# cnc_rev_1.net
KiCad netlist of a schematic drawn in EAGLE
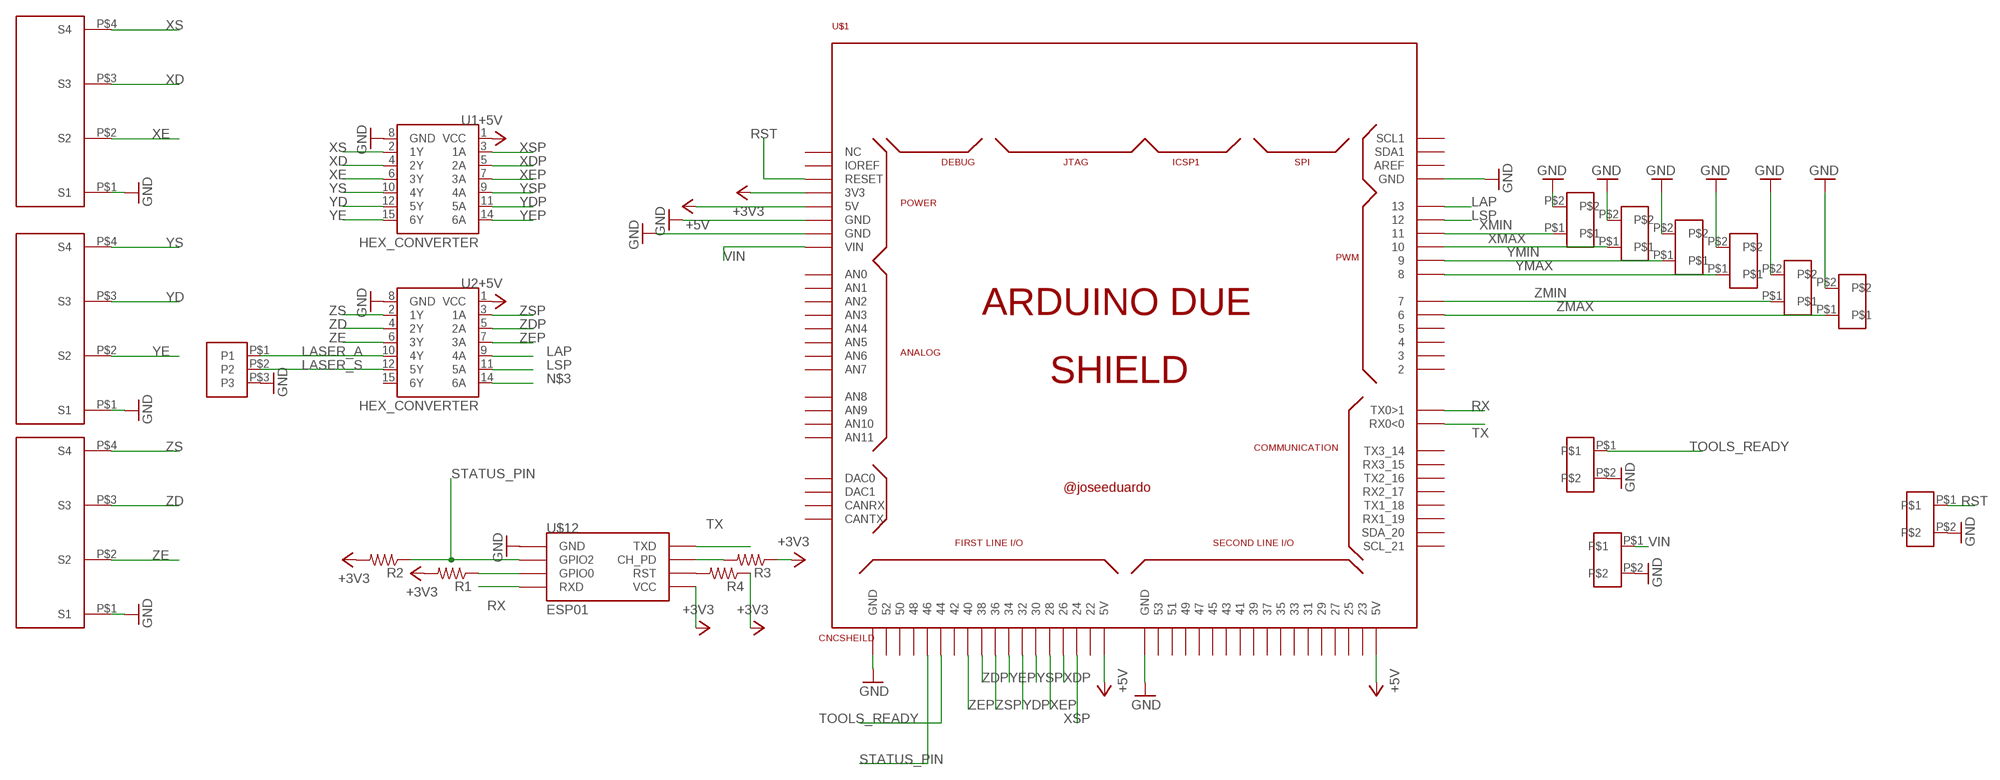
[diagram p0: schematic, sheet 1]

(export (version "E")
  (design (tool "Eeschema 10.0.6"))
  (components
    (comp (ref "INPUT")
      (value "PIN_LOCK_1X2")
      (footprint "eagle-import:PIN_LOCK1X2")
      (libsource (lib "eagle-import") (part "PIN_LOCK_1X2"))
    )
    (comp (ref "INPUT1")
      (value "PIN_LOCK_1X2")
      (footprint "eagle-import:PIN_LOCK1X2")
      (libsource (lib "eagle-import") (part "PIN_LOCK_1X2"))
    )
    (comp (ref "R1")
      (value "0.1OHM-1/2W-1%(1210)")
      (footprint "eagle-import:1210")
      (libsource (lib "eagle-import") (part "0.1OHM-1/2W-1%(1210)"))
    )
    (comp (ref "R2")
      (value "0.1OHM-1/2W-1%(1210)")
      (footprint "eagle-import:1210")
      (libsource (lib "eagle-import") (part "0.1OHM-1/2W-1%(1210)"))
    )
    (comp (ref "R3")
      (value "0.1OHM-1/2W-1%(1210)")
      (footprint "eagle-import:1210")
      (libsource (lib "eagle-import") (part "0.1OHM-1/2W-1%(1210)"))
    )
    (comp (ref "R4")
      (value "0.1OHM-1/2W-1%(1210)")
      (footprint "eagle-import:1210")
      (libsource (lib "eagle-import") (part "0.1OHM-1/2W-1%(1210)"))
    )
    (comp (ref "U$1")
      (value "CNCSHEILD")
      (footprint "eagle-import:CNCSHEILD")
      (libsource (lib "eagle-import") (part "CNCSHEILD"))
    )
    (comp (ref "U$2")
      (value "TBC1X4")
      (footprint "eagle-import:PTC1X4")
      (libsource (lib "eagle-import") (part "TBC1X4"))
    )
    (comp (ref "U$3")
      (value "TBC1X4")
      (footprint "eagle-import:PTC1X4")
      (libsource (lib "eagle-import") (part "TBC1X4"))
    )
    (comp (ref "U$4")
      (value "TBC1X4")
      (footprint "eagle-import:PTC1X4")
      (libsource (lib "eagle-import") (part "TBC1X4"))
    )
    (comp (ref "U$5")
      (value "PIN_LOCK_1X2")
      (footprint "eagle-import:PIN_LOCK1X2")
      (libsource (lib "eagle-import") (part "PIN_LOCK_1X2"))
    )
    (comp (ref "U$6")
      (value "PIN_LOCK_1X2")
      (footprint "eagle-import:PIN_LOCK1X2")
      (libsource (lib "eagle-import") (part "PIN_LOCK_1X2"))
    )
    (comp (ref "U$7")
      (value "PIN_LOCK_1X2")
      (footprint "eagle-import:PIN_LOCK1X2")
      (libsource (lib "eagle-import") (part "PIN_LOCK_1X2"))
    )
    (comp (ref "U$8")
      (value "PIN_LOCK_1X2")
      (footprint "eagle-import:PIN_LOCK1X2")
      (libsource (lib "eagle-import") (part "PIN_LOCK_1X2"))
    )
    (comp (ref "U$9")
      (value "PIN_LOCK_1X2")
      (footprint "eagle-import:PIN_LOCK1X2")
      (libsource (lib "eagle-import") (part "PIN_LOCK_1X2"))
    )
    (comp (ref "U$10")
      (value "PIN_LOCK_1X2")
      (footprint "eagle-import:PIN_LOCK1X2")
      (libsource (lib "eagle-import") (part "PIN_LOCK_1X2"))
    )
    (comp (ref "U$11")
      (value "PIN_LOCK_1X2")
      (footprint "eagle-import:PIN_LOCK1X2")
      (libsource (lib "eagle-import") (part "PIN_LOCK_1X2"))
    )
    (comp (ref "U$12")
      (value "ESP01")
      (footprint "eagle-import:ESP01")
      (libsource (lib "eagle-import") (part "ESP01"))
    )
    (comp (ref "U$13")
      (value "PIN_LOCK_1X3")
      (footprint "eagle-import:PIN_LOCK1X3")
      (libsource (lib "eagle-import") (part "PIN_LOCK_1X3"))
    )
    (comp (ref "U1")
      (value "HEX_CONVERTER")
      (footprint "eagle-import:SO016")
      (libsource (lib "eagle-import") (part "HEX_CONVERTER"))
    )
    (comp (ref "U2")
      (value "HEX_CONVERTER")
      (footprint "eagle-import:SO016")
      (libsource (lib "eagle-import") (part "HEX_CONVERTER"))
    )
  )
  (nets
    (net (code "1") (name "+3V3") (class "Default")
      (node (ref "R1") (pin "2") (pinfunction "2_2") (pintype "passive"))
      (node (ref "R2") (pin "2") (pinfunction "2_2") (pintype "passive"))
      (node (ref "R3") (pin "1") (pinfunction "1_1") (pintype "passive"))
      (node (ref "R4") (pin "1") (pinfunction "1_1") (pintype "passive"))
      (node (ref "U$1") (pin "3V3") (pinfunction "3V3_3V3") (pintype "bidirectional"))
      (node (ref "U$12") (pin "VCC") (pinfunction "VCC_VCC") (pintype "bidirectional"))
    )
    (net (code "2") (name "+5V") (class "Default")
      (node (ref "U$1") (pin "5V0") (pinfunction "5V_5V0") (pintype "bidirectional"))
      (node (ref "U$1") (pin "5V0_1") (pinfunction "5V_5V0_1") (pintype "bidirectional"))
      (node (ref "U$1") (pin "5V0_2") (pinfunction "5V_5V0_2") (pintype "bidirectional"))
      (node (ref "U1") (pin "1") (pinfunction "VCC_1") (pintype "bidirectional"))
      (node (ref "U2") (pin "1") (pinfunction "VCC_1") (pintype "bidirectional"))
    )
    (net (code "3") (name "/LAP") (class "Default")
      (node (ref "U$1") (pin "13") (pinfunction "13_13") (pintype "bidirectional"))
      (node (ref "U2") (pin "9") (pinfunction "4A_9") (pintype "bidirectional"))
    )
    (net (code "4") (name "/LASER_A") (class "Default")
      (node (ref "U$13") (pin "P$1") (pinfunction "P1_P$1") (pintype "bidirectional"))
      (node (ref "U2") (pin "10") (pinfunction "4Y_10") (pintype "bidirectional"))
    )
    (net (code "5") (name "/LASER_S") (class "Default")
      (node (ref "U$13") (pin "P$2") (pinfunction "P2_P$2") (pintype "bidirectional"))
      (node (ref "U2") (pin "12") (pinfunction "5Y_12") (pintype "bidirectional"))
    )
    (net (code "6") (name "/LSP") (class "Default")
      (node (ref "U$1") (pin "12") (pinfunction "12_12") (pintype "bidirectional"))
      (node (ref "U2") (pin "11") (pinfunction "5A_11") (pintype "bidirectional"))
    )
    (net (code "7") (name "/N$3") (class "Default")
      (node (ref "U2") (pin "14") (pinfunction "6A_14") (pintype "bidirectional"))
    )
    (net (code "8") (name "/RST") (class "Default")
      (node (ref "U$1") (pin "RESET") (pinfunction "RESET_RESET") (pintype "bidirectional"))
      (node (ref "U$11") (pin "P$1") (pinfunction "P$1_P$1") (pintype "bidirectional"))
    )
    (net (code "9") (name "/RX") (class "Default")
      (node (ref "U$1") (pin "1") (pinfunction "TX0>1_1") (pintype "bidirectional"))
      (node (ref "U$12") (pin "RX") (pinfunction "RXD_RX") (pintype "bidirectional"))
    )
    (net (code "10") (name "/STATUS_PIN") (class "Default")
      (node (ref "R2") (pin "1") (pinfunction "1_1") (pintype "passive"))
      (node (ref "U$1") (pin "46") (pinfunction "46_46") (pintype "bidirectional"))
      (node (ref "U$12") (pin "GPIO2") (pinfunction "GPIO2_GPIO2") (pintype "bidirectional"))
    )
    (net (code "11") (name "/TOOLS_READY") (class "Default")
      (node (ref "INPUT1") (pin "P$1") (pinfunction "P$1_P$1") (pintype "bidirectional"))
      (node (ref "U$1") (pin "44") (pinfunction "44_44") (pintype "bidirectional"))
    )
    (net (code "12") (name "/TX") (class "Default")
      (node (ref "U$1") (pin "0") (pinfunction "RX0<0_0") (pintype "bidirectional"))
      (node (ref "U$12") (pin "TX") (pinfunction "TXD_TX") (pintype "bidirectional"))
    )
    (net (code "13") (name "/VIN") (class "Default")
      (node (ref "INPUT") (pin "P$1") (pinfunction "P$1_P$1") (pintype "bidirectional"))
      (node (ref "U$1") (pin "VIN") (pinfunction "VIN_VIN") (pintype "bidirectional"))
    )
    (net (code "14") (name "/XD") (class "Default")
      (node (ref "U$4") (pin "P$3") (pinfunction "S3_P$3") (pintype "bidirectional"))
      (node (ref "U1") (pin "4") (pinfunction "2Y_4") (pintype "bidirectional"))
    )
    (net (code "15") (name "/XDP") (class "Default")
      (node (ref "U$1") (pin "26") (pinfunction "26_26") (pintype "bidirectional"))
      (node (ref "U1") (pin "5") (pinfunction "2A_5") (pintype "bidirectional"))
    )
    (net (code "16") (name "/XE") (class "Default")
      (node (ref "U$4") (pin "P$2") (pinfunction "S2_P$2") (pintype "bidirectional"))
      (node (ref "U1") (pin "6") (pinfunction "3Y_6") (pintype "bidirectional"))
    )
    (net (code "17") (name "/XEP") (class "Default")
      (node (ref "U$1") (pin "28") (pinfunction "28_28") (pintype "bidirectional"))
      (node (ref "U1") (pin "7") (pinfunction "3A_7") (pintype "bidirectional"))
    )
    (net (code "18") (name "/XMAX") (class "Default")
      (node (ref "U$1") (pin "10") (pinfunction "10_10") (pintype "bidirectional"))
      (node (ref "U$8") (pin "P$1") (pinfunction "P$1_P$1") (pintype "bidirectional"))
    )
    (net (code "19") (name "/XMIN") (class "Default")
      (node (ref "U$1") (pin "11") (pinfunction "11_11") (pintype "bidirectional"))
      (node (ref "U$5") (pin "P$1") (pinfunction "P$1_P$1") (pintype "bidirectional"))
    )
    (net (code "20") (name "/XS") (class "Default")
      (node (ref "U$4") (pin "P$4") (pinfunction "S4_P$4") (pintype "bidirectional"))
      (node (ref "U1") (pin "2") (pinfunction "1Y_2") (pintype "bidirectional"))
    )
    (net (code "21") (name "/XSP") (class "Default")
      (node (ref "U$1") (pin "24") (pinfunction "24_24") (pintype "bidirectional"))
      (node (ref "U1") (pin "3") (pinfunction "1A_3") (pintype "bidirectional"))
    )
    (net (code "22") (name "/YD") (class "Default")
      (node (ref "U$2") (pin "P$3") (pinfunction "S3_P$3") (pintype "bidirectional"))
      (node (ref "U1") (pin "12") (pinfunction "5Y_12") (pintype "bidirectional"))
    )
    (net (code "23") (name "/YDP") (class "Default")
      (node (ref "U$1") (pin "32") (pinfunction "32_32") (pintype "bidirectional"))
      (node (ref "U1") (pin "11") (pinfunction "5A_11") (pintype "bidirectional"))
    )
    (net (code "24") (name "/YE") (class "Default")
      (node (ref "U$2") (pin "P$2") (pinfunction "S2_P$2") (pintype "bidirectional"))
      (node (ref "U1") (pin "15") (pinfunction "6Y_15") (pintype "bidirectional"))
    )
    (net (code "25") (name "/YEP") (class "Default")
      (node (ref "U$1") (pin "34") (pinfunction "34_34") (pintype "bidirectional"))
      (node (ref "U1") (pin "14") (pinfunction "6A_14") (pintype "bidirectional"))
    )
    (net (code "26") (name "/YMAX") (class "Default")
      (node (ref "U$1") (pin "8") (pinfunction "8_8") (pintype "bidirectional"))
      (node (ref "U$9") (pin "P$1") (pinfunction "P$1_P$1") (pintype "bidirectional"))
    )
    (net (code "27") (name "/YMIN") (class "Default")
      (node (ref "U$1") (pin "9") (pinfunction "9_9") (pintype "bidirectional"))
      (node (ref "U$6") (pin "P$1") (pinfunction "P$1_P$1") (pintype "bidirectional"))
    )
    (net (code "28") (name "/YS") (class "Default")
      (node (ref "U$2") (pin "P$4") (pinfunction "S4_P$4") (pintype "bidirectional"))
      (node (ref "U1") (pin "10") (pinfunction "4Y_10") (pintype "bidirectional"))
    )
    (net (code "29") (name "/YSP") (class "Default")
      (node (ref "U$1") (pin "30") (pinfunction "30_30") (pintype "bidirectional"))
      (node (ref "U1") (pin "9") (pinfunction "4A_9") (pintype "bidirectional"))
    )
    (net (code "30") (name "/ZD") (class "Default")
      (node (ref "U$3") (pin "P$3") (pinfunction "S3_P$3") (pintype "bidirectional"))
      (node (ref "U2") (pin "4") (pinfunction "2Y_4") (pintype "bidirectional"))
    )
    (net (code "31") (name "/ZDP") (class "Default")
      (node (ref "U$1") (pin "38") (pinfunction "38_38") (pintype "bidirectional"))
      (node (ref "U2") (pin "5") (pinfunction "2A_5") (pintype "bidirectional"))
    )
    (net (code "32") (name "/ZE") (class "Default")
      (node (ref "U$3") (pin "P$2") (pinfunction "S2_P$2") (pintype "bidirectional"))
      (node (ref "U2") (pin "6") (pinfunction "3Y_6") (pintype "bidirectional"))
    )
    (net (code "33") (name "/ZEP") (class "Default")
      (node (ref "U$1") (pin "40") (pinfunction "40_40") (pintype "bidirectional"))
      (node (ref "U2") (pin "7") (pinfunction "3A_7") (pintype "bidirectional"))
    )
    (net (code "34") (name "/ZMAX") (class "Default")
      (node (ref "U$1") (pin "6") (pinfunction "6_6") (pintype "bidirectional"))
      (node (ref "U$10") (pin "P$1") (pinfunction "P$1_P$1") (pintype "bidirectional"))
    )
    (net (code "35") (name "/ZMIN") (class "Default")
      (node (ref "U$1") (pin "7") (pinfunction "7_7") (pintype "bidirectional"))
      (node (ref "U$7") (pin "P$1") (pinfunction "P$1_P$1") (pintype "bidirectional"))
    )
    (net (code "36") (name "/ZS") (class "Default")
      (node (ref "U$3") (pin "P$4") (pinfunction "S4_P$4") (pintype "bidirectional"))
      (node (ref "U2") (pin "2") (pinfunction "1Y_2") (pintype "bidirectional"))
    )
    (net (code "37") (name "/ZSP") (class "Default")
      (node (ref "U$1") (pin "36") (pinfunction "36_36") (pintype "bidirectional"))
      (node (ref "U2") (pin "3") (pinfunction "1A_3") (pintype "bidirectional"))
    )
    (net (code "38") (name "GND") (class "Default")
      (node (ref "INPUT") (pin "P$2") (pinfunction "P$2_P$2") (pintype "bidirectional"))
      (node (ref "INPUT1") (pin "P$2") (pinfunction "P$2_P$2") (pintype "bidirectional"))
      (node (ref "U$1") (pin "GND") (pinfunction "GND_GND") (pintype "bidirectional"))
      (node (ref "U$1") (pin "GND_1") (pinfunction "GND_GND_1") (pintype "bidirectional"))
      (node (ref "U$1") (pin "GND_2") (pinfunction "GND_GND_2") (pintype "bidirectional"))
      (node (ref "U$1") (pin "GND_3") (pinfunction "GND_GND_3") (pintype "bidirectional"))
      (node (ref "U$1") (pin "GND_4") (pinfunction "GND_GND_4") (pintype "bidirectional"))
      (node (ref "U$10") (pin "P$2") (pinfunction "P$2_P$2") (pintype "bidirectional"))
      (node (ref "U$11") (pin "P$2") (pinfunction "P$2_P$2") (pintype "bidirectional"))
      (node (ref "U$2") (pin "P$1") (pinfunction "S1_P$1") (pintype "bidirectional"))
      (node (ref "U$3") (pin "P$1") (pinfunction "S1_P$1") (pintype "bidirectional"))
      (node (ref "U$4") (pin "P$1") (pinfunction "S1_P$1") (pintype "bidirectional"))
      (node (ref "U$5") (pin "P$2") (pinfunction "P$2_P$2") (pintype "bidirectional"))
      (node (ref "U$6") (pin "P$2") (pinfunction "P$2_P$2") (pintype "bidirectional"))
      (node (ref "U$7") (pin "P$2") (pinfunction "P$2_P$2") (pintype "bidirectional"))
      (node (ref "U$8") (pin "P$2") (pinfunction "P$2_P$2") (pintype "bidirectional"))
      (node (ref "U$9") (pin "P$2") (pinfunction "P$2_P$2") (pintype "bidirectional"))
    )
    (net (code "39") (name "Net-(R1-Pad1)") (class "Default")
      (node (ref "R1") (pin "1") (pinfunction "1_1") (pintype "passive"))
      (node (ref "U$12") (pin "GPIO0") (pinfunction "GPIO0_GPIO0") (pintype "bidirectional"))
    )
    (net (code "40") (name "Net-(R3-Pad2)") (class "Default")
      (node (ref "R3") (pin "2") (pinfunction "2_2") (pintype "passive"))
      (node (ref "U$12") (pin "CH_PD") (pinfunction "CH_PD_CH_PD") (pintype "bidirectional"))
    )
    (net (code "41") (name "Net-(R4-Pad2)") (class "Default")
      (node (ref "R4") (pin "2") (pinfunction "2_2") (pintype "passive"))
      (node (ref "U$12") (pin "RST") (pinfunction "RST_RST") (pintype "bidirectional"))
    )
    (net (code "42") (name "unconnected-(U$1-AN0-PadA0)") (class "Default")
      (node (ref "U$1") (pin "A0") (pinfunction "AN0_A0") (pintype "bidirectional"))
    )
    (net (code "43") (name "unconnected-(U$1-AN1-PadA1)") (class "Default")
      (node (ref "U$1") (pin "A1") (pinfunction "AN1_A1") (pintype "bidirectional"))
    )
    (net (code "44") (name "unconnected-(U$1-AN2-PadA2)") (class "Default")
      (node (ref "U$1") (pin "A2") (pinfunction "AN2_A2") (pintype "bidirectional"))
    )
    (net (code "45") (name "unconnected-(U$1-AN3-PadA3)") (class "Default")
      (node (ref "U$1") (pin "A3") (pinfunction "AN3_A3") (pintype "bidirectional"))
    )
    (net (code "46") (name "unconnected-(U$1-AN4-PadA4)") (class "Default")
      (node (ref "U$1") (pin "A4") (pinfunction "AN4_A4") (pintype "bidirectional"))
    )
    (net (code "47") (name "unconnected-(U$1-AN5-PadA5)") (class "Default")
      (node (ref "U$1") (pin "A5") (pinfunction "AN5_A5") (pintype "bidirectional"))
    )
    (net (code "48") (name "unconnected-(U$1-AN6-PadA6)") (class "Default")
      (node (ref "U$1") (pin "A6") (pinfunction "AN6_A6") (pintype "bidirectional"))
    )
    (net (code "49") (name "unconnected-(U$1-AN7-PadA7)") (class "Default")
      (node (ref "U$1") (pin "A7") (pinfunction "AN7_A7") (pintype "bidirectional"))
    )
    (net (code "50") (name "unconnected-(U$1-AN8-PadA8)") (class "Default")
      (node (ref "U$1") (pin "A8") (pinfunction "AN8_A8") (pintype "bidirectional"))
    )
    (net (code "51") (name "unconnected-(U$1-AN9-PadA9)") (class "Default")
      (node (ref "U$1") (pin "A9") (pinfunction "AN9_A9") (pintype "bidirectional"))
    )
    (net (code "52") (name "unconnected-(U$1-AN10-PadA10)") (class "Default")
      (node (ref "U$1") (pin "A10") (pinfunction "AN10_A10") (pintype "bidirectional"))
    )
    (net (code "53") (name "unconnected-(U$1-AN11-PadA11)") (class "Default")
      (node (ref "U$1") (pin "A11") (pinfunction "AN11_A11") (pintype "bidirectional"))
    )
    (net (code "54") (name "unconnected-(U$1-NC-PadNC_2)") (class "Default")
      (node (ref "U$1") (pin "NC_2") (pinfunction "NC_NC_2") (pintype "no_connect"))
    )
    (net (code "55") (name "unconnected-(U$1-Pad2)") (class "Default")
      (node (ref "U$1") (pin "2") (pinfunction "2_2") (pintype "bidirectional"))
    )
    (net (code "56") (name "unconnected-(U$1-Pad3)") (class "Default")
      (node (ref "U$1") (pin "3") (pinfunction "3_3") (pintype "bidirectional"))
    )
    (net (code "57") (name "unconnected-(U$1-Pad4)") (class "Default")
      (node (ref "U$1") (pin "4") (pinfunction "4_4") (pintype "bidirectional"))
    )
    (net (code "58") (name "unconnected-(U$1-Pad5)") (class "Default")
      (node (ref "U$1") (pin "5") (pinfunction "5_5") (pintype "bidirectional"))
    )
    (net (code "59") (name "unconnected-(U$1-Pad22)") (class "Default")
      (node (ref "U$1") (pin "22") (pinfunction "22_22") (pintype "bidirectional"))
    )
    (net (code "60") (name "unconnected-(U$1-Pad23)") (class "Default")
      (node (ref "U$1") (pin "23") (pinfunction "23_23") (pintype "bidirectional"))
    )
    (net (code "61") (name "unconnected-(U$1-Pad25)") (class "Default")
      (node (ref "U$1") (pin "25") (pinfunction "25_25") (pintype "bidirectional"))
    )
    (net (code "62") (name "unconnected-(U$1-Pad27)") (class "Default")
      (node (ref "U$1") (pin "27") (pinfunction "27_27") (pintype "bidirectional"))
    )
    (net (code "63") (name "unconnected-(U$1-Pad29)") (class "Default")
      (node (ref "U$1") (pin "29") (pinfunction "29_29") (pintype "bidirectional"))
    )
    (net (code "64") (name "unconnected-(U$1-Pad31)") (class "Default")
      (node (ref "U$1") (pin "31") (pinfunction "31_31") (pintype "bidirectional"))
    )
    (net (code "65") (name "unconnected-(U$1-Pad33)") (class "Default")
      (node (ref "U$1") (pin "33") (pinfunction "33_33") (pintype "bidirectional"))
    )
    (net (code "66") (name "unconnected-(U$1-Pad35)") (class "Default")
      (node (ref "U$1") (pin "35") (pinfunction "35_35") (pintype "bidirectional"))
    )
    (net (code "67") (name "unconnected-(U$1-Pad37)") (class "Default")
      (node (ref "U$1") (pin "37") (pinfunction "37_37") (pintype "bidirectional"))
    )
    (net (code "68") (name "unconnected-(U$1-Pad39)") (class "Default")
      (node (ref "U$1") (pin "39") (pinfunction "39_39") (pintype "bidirectional"))
    )
    (net (code "69") (name "unconnected-(U$1-Pad41)") (class "Default")
      (node (ref "U$1") (pin "41") (pinfunction "41_41") (pintype "bidirectional"))
    )
    (net (code "70") (name "unconnected-(U$1-Pad42)") (class "Default")
      (node (ref "U$1") (pin "42") (pinfunction "42_42") (pintype "bidirectional"))
    )
    (net (code "71") (name "unconnected-(U$1-Pad43)") (class "Default")
      (node (ref "U$1") (pin "43") (pinfunction "43_43") (pintype "bidirectional"))
    )
    (net (code "72") (name "unconnected-(U$1-Pad45)") (class "Default")
      (node (ref "U$1") (pin "45") (pinfunction "45_45") (pintype "bidirectional"))
    )
    (net (code "73") (name "unconnected-(U$1-Pad47)") (class "Default")
      (node (ref "U$1") (pin "47") (pinfunction "47_47") (pintype "bidirectional"))
    )
    (net (code "74") (name "unconnected-(U$1-Pad48)") (class "Default")
      (node (ref "U$1") (pin "48") (pinfunction "48_48") (pintype "bidirectional"))
    )
    (net (code "75") (name "unconnected-(U$1-Pad49)") (class "Default")
      (node (ref "U$1") (pin "49") (pinfunction "49_49") (pintype "bidirectional"))
    )
    (net (code "76") (name "unconnected-(U$1-Pad50)") (class "Default")
      (node (ref "U$1") (pin "50") (pinfunction "50_50") (pintype "bidirectional"))
    )
    (net (code "77") (name "unconnected-(U$1-Pad51)") (class "Default")
      (node (ref "U$1") (pin "51") (pinfunction "51_51") (pintype "bidirectional"))
    )
    (net (code "78") (name "unconnected-(U$1-Pad52)") (class "Default")
      (node (ref "U$1") (pin "52") (pinfunction "52_52") (pintype "bidirectional"))
    )
    (net (code "79") (name "unconnected-(U$1-Pad53)") (class "Default")
      (node (ref "U$1") (pin "53") (pinfunction "53_53") (pintype "bidirectional"))
    )
    (net (code "80") (name "unconnected-(U$1-PadAREF)") (class "Default")
      (node (ref "U$1") (pin "AREF") (pinfunction "AREF_AREF") (pintype "bidirectional"))
    )
    (net (code "81") (name "unconnected-(U$1-PadCANRX)") (class "Default")
      (node (ref "U$1") (pin "CANRX") (pinfunction "CANRX_CANRX") (pintype "bidirectional"))
    )
    (net (code "82") (name "unconnected-(U$1-PadCANTX)") (class "Default")
      (node (ref "U$1") (pin "CANTX") (pinfunction "CANTX_CANTX") (pintype "bidirectional"))
    )
    (net (code "83") (name "unconnected-(U$1-PadDAC0)") (class "Default")
      (node (ref "U$1") (pin "DAC0") (pinfunction "DAC0_DAC0") (pintype "bidirectional"))
    )
    (net (code "84") (name "unconnected-(U$1-PadDAC1)") (class "Default")
      (node (ref "U$1") (pin "DAC1") (pinfunction "DAC1_DAC1") (pintype "bidirectional"))
    )
    (net (code "85") (name "unconnected-(U$1-PadIOREF)") (class "Default")
      (node (ref "U$1") (pin "IOREF") (pinfunction "IOREF_IOREF") (pintype "bidirectional"))
    )
    (net (code "86") (name "unconnected-(U$1-PadSCL1)") (class "Default")
      (node (ref "U$1") (pin "SCL1") (pinfunction "SCL1_SCL1") (pintype "bidirectional"))
    )
    (net (code "87") (name "unconnected-(U$1-PadSDA1)") (class "Default")
      (node (ref "U$1") (pin "SDA1") (pinfunction "SDA1_SDA1") (pintype "bidirectional"))
    )
    (net (code "88") (name "unconnected-(U$1-RX1_19-Pad19)") (class "Default")
      (node (ref "U$1") (pin "19") (pinfunction "RX1_19_19") (pintype "bidirectional"))
    )
    (net (code "89") (name "unconnected-(U$1-RX2_17-Pad17)") (class "Default")
      (node (ref "U$1") (pin "17") (pinfunction "RX2_17_17") (pintype "bidirectional"))
    )
    (net (code "90") (name "unconnected-(U$1-RX3_15-Pad15)") (class "Default")
      (node (ref "U$1") (pin "15") (pinfunction "RX3_15_15") (pintype "bidirectional"))
    )
    (net (code "91") (name "unconnected-(U$1-SCL_21-Pad21)") (class "Default")
      (node (ref "U$1") (pin "21") (pinfunction "SCL_21_21") (pintype "bidirectional"))
    )
    (net (code "92") (name "unconnected-(U$1-SDA_20-Pad20)") (class "Default")
      (node (ref "U$1") (pin "20") (pinfunction "SDA_20_20") (pintype "bidirectional"))
    )
    (net (code "93") (name "unconnected-(U$1-TX1_18-Pad18)") (class "Default")
      (node (ref "U$1") (pin "18") (pinfunction "TX1_18_18") (pintype "bidirectional"))
    )
    (net (code "94") (name "unconnected-(U$1-TX2_16-Pad16)") (class "Default")
      (node (ref "U$1") (pin "16") (pinfunction "TX2_16_16") (pintype "bidirectional"))
    )
    (net (code "95") (name "unconnected-(U$1-TX3_14-Pad14)") (class "Default")
      (node (ref "U$1") (pin "14") (pinfunction "TX3_14_14") (pintype "bidirectional"))
    )
    (net (code "96") (name "unconnected-(U$12-PadGND)") (class "Default")
      (node (ref "U$12") (pin "GND") (pinfunction "GND_GND") (pintype "bidirectional"))
    )
    (net (code "97") (name "unconnected-(U$13-P3-PadP$3)") (class "Default")
      (node (ref "U$13") (pin "P$3") (pinfunction "P3_P$3") (pintype "bidirectional"))
    )
    (net (code "98") (name "unconnected-(U1-GND-Pad8)") (class "Default")
      (node (ref "U1") (pin "8") (pinfunction "GND_8") (pintype "bidirectional"))
    )
    (net (code "99") (name "unconnected-(U2-6Y-Pad15)") (class "Default")
      (node (ref "U2") (pin "15") (pinfunction "6Y_15") (pintype "bidirectional"))
    )
    (net (code "100") (name "unconnected-(U2-GND-Pad8)") (class "Default")
      (node (ref "U2") (pin "8") (pinfunction "GND_8") (pintype "bidirectional"))
    )
  )
)
